# AS5040_SSI.net
KiCad netlist of a schematic drawn in EAGLE
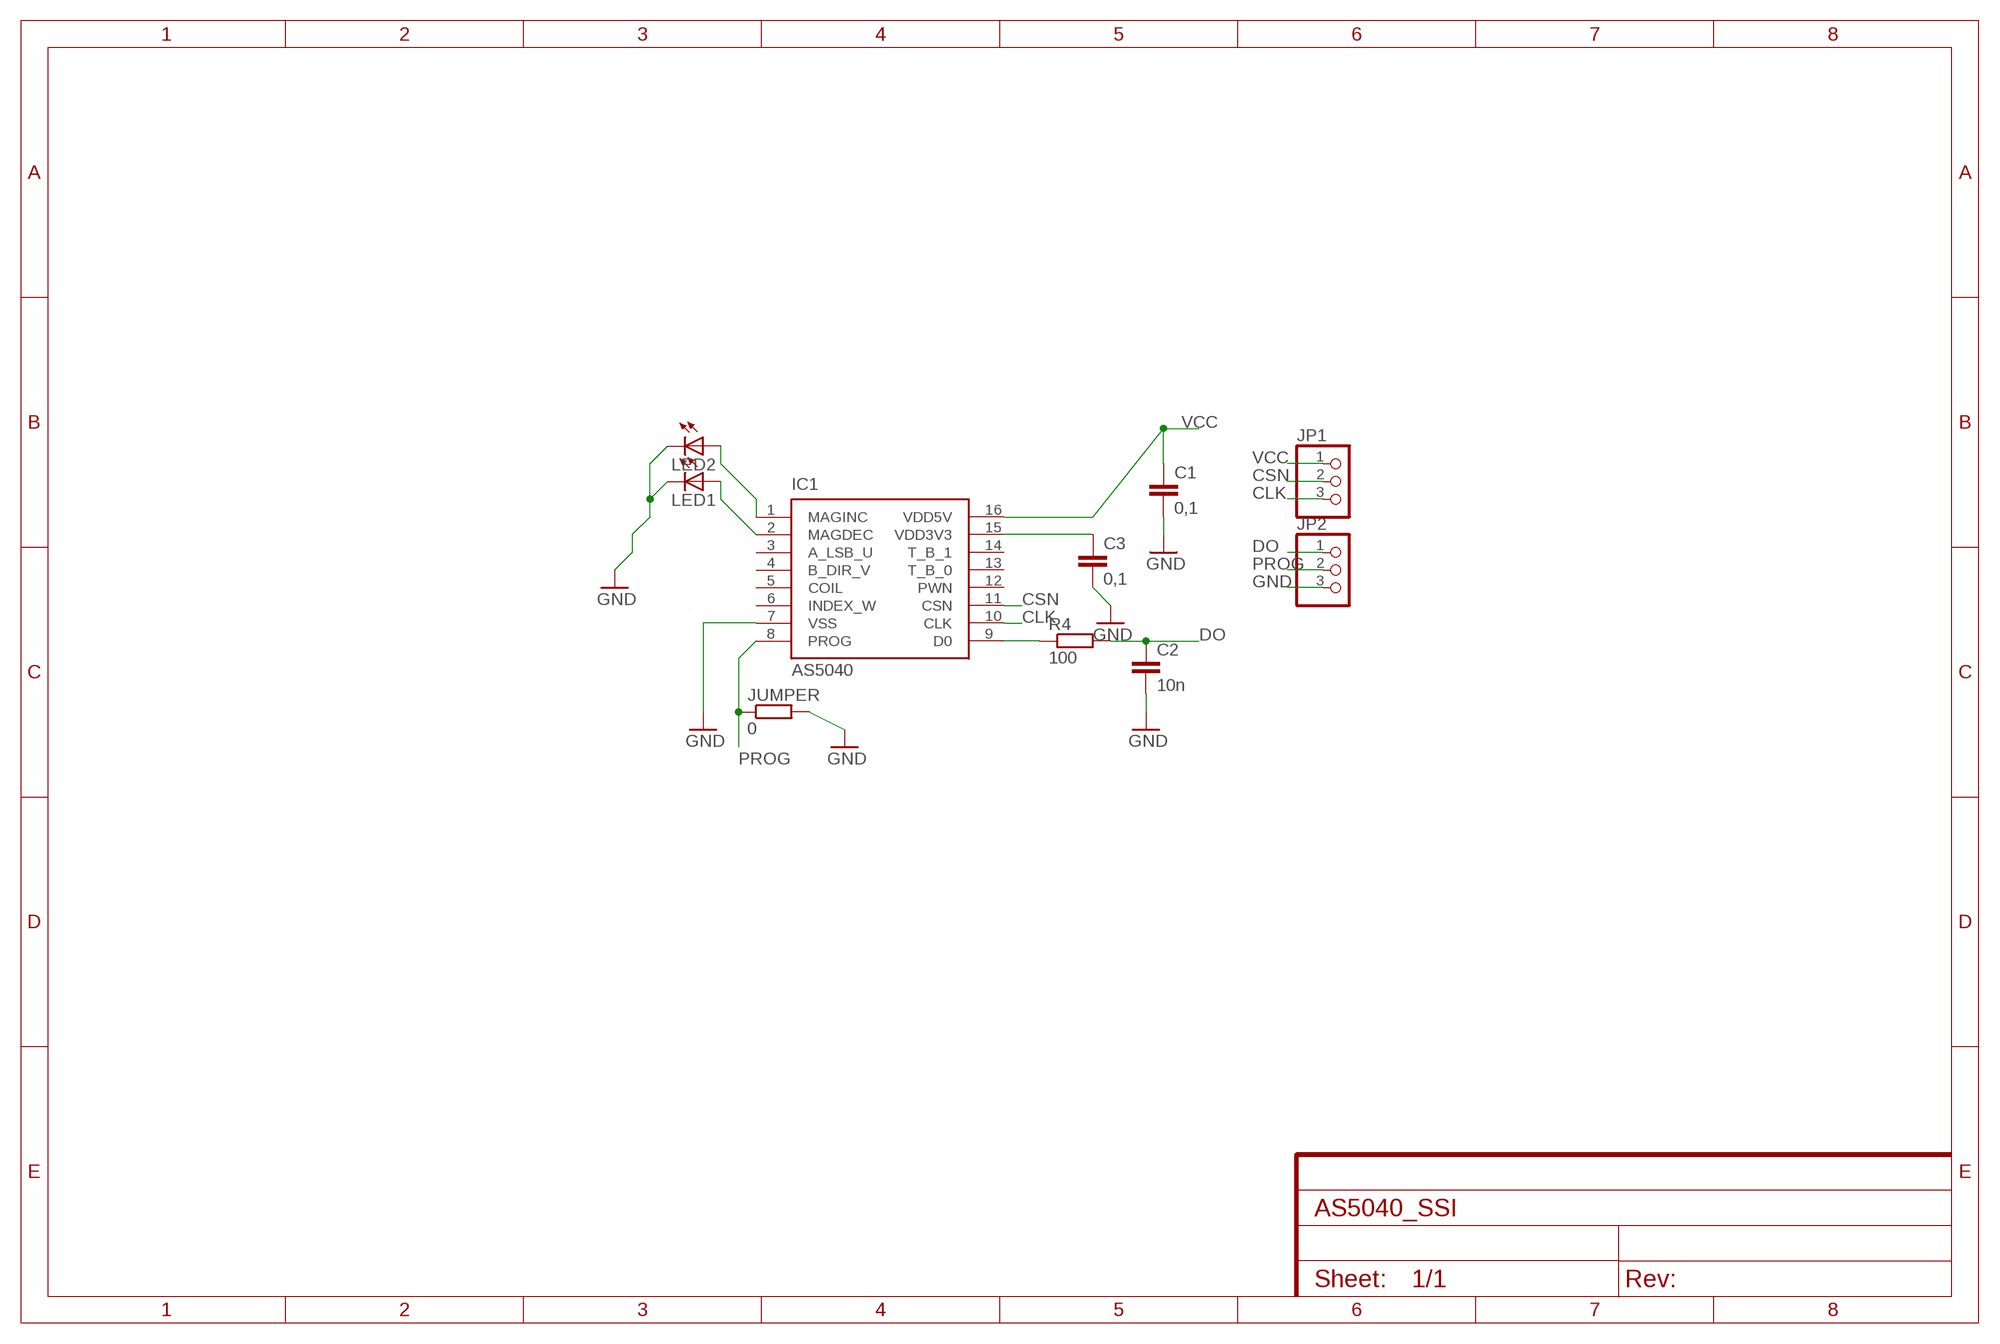
[diagram p0: schematic, sheet 1]

(export (version "E")
  (design (tool "Eeschema 10.0.6"))
  (components
    (comp (ref "C1")
      (value "0,1")
      (footprint "eagle-import:C0805")
      (libsource (lib "eagle-import") (part "C-EUC0805"))
    )
    (comp (ref "C2")
      (value "10n")
      (footprint "eagle-import:C0805")
      (libsource (lib "eagle-import") (part "C-EUC0805"))
    )
    (comp (ref "C3")
      (value "0,1")
      (footprint "eagle-import:C0805")
      (libsource (lib "eagle-import") (part "C-EUC0805"))
    )
    (comp (ref "IC1")
      (value "AS5040")
      (footprint "eagle-import:SSOP16")
      (fields (field (name "MPN") "AS5040ASSU"))
      (libsource (lib "eagle-import") (part "AS5040"))
    )
    (comp (ref "JP1")
      (value "PINHD-1X3")
      (footprint "eagle-import:1X03")
      (libsource (lib "eagle-import") (part "PINHD-1X3"))
    )
    (comp (ref "JP2")
      (value "PINHD-1X3")
      (footprint "eagle-import:1X03")
      (libsource (lib "eagle-import") (part "PINHD-1X3"))
    )
    (comp (ref "JUMPER")
      (value "0")
      (footprint "eagle-import:M0805")
      (libsource (lib "eagle-import") (part "R-EU_M0805"))
    )
    (comp (ref "LED1")
      (value "LEDCHIPLED_0805")
      (footprint "eagle-import:CHIPLED_0805")
      (libsource (lib "eagle-import") (part "LEDCHIPLED_0805"))
    )
    (comp (ref "LED2")
      (value "LEDCHIPLED_0805")
      (footprint "eagle-import:CHIPLED_0805")
      (libsource (lib "eagle-import") (part "LEDCHIPLED_0805"))
    )
    (comp (ref "R4")
      (value "100")
      (footprint "eagle-import:M0805")
      (libsource (lib "eagle-import") (part "R-EU_M0805"))
    )
  )
  (nets
    (net (code "1") (name "/CLK") (class "Default")
      (node (ref "IC1") (pin "10") (pinfunction "CLK_10") (pintype "input"))
      (node (ref "JP1") (pin "3") (pinfunction "3_3") (pintype "passive"))
    )
    (net (code "2") (name "/CSN") (class "Default")
      (node (ref "IC1") (pin "11") (pinfunction "CSN_11") (pintype "input"))
      (node (ref "JP1") (pin "2") (pinfunction "2_2") (pintype "passive"))
    )
    (net (code "3") (name "/DO") (class "Default")
      (node (ref "C2") (pin "1") (pinfunction "1_1") (pintype "passive"))
      (node (ref "JP2") (pin "1") (pinfunction "1_1") (pintype "passive"))
      (node (ref "R4") (pin "2") (pinfunction "2_2") (pintype "passive"))
    )
    (net (code "4") (name "/PROG") (class "Default")
      (node (ref "IC1") (pin "8") (pinfunction "PROG_8") (pintype "input"))
      (node (ref "JP2") (pin "2") (pinfunction "2_2") (pintype "passive"))
      (node (ref "JUMPER") (pin "1") (pinfunction "1_1") (pintype "passive"))
    )
    (net (code "5") (name "/VCC") (class "Default")
      (node (ref "C1") (pin "1") (pinfunction "1_1") (pintype "passive"))
      (node (ref "IC1") (pin "16") (pinfunction "VDD5V_16") (pintype "passive"))
      (node (ref "JP1") (pin "1") (pinfunction "1_1") (pintype "passive"))
    )
    (net (code "6") (name "GND") (class "Default")
      (node (ref "C1") (pin "2") (pinfunction "2_2") (pintype "passive"))
      (node (ref "C2") (pin "2") (pinfunction "2_2") (pintype "passive"))
      (node (ref "C3") (pin "2") (pinfunction "2_2") (pintype "passive"))
      (node (ref "IC1") (pin "7") (pinfunction "VSS_7") (pintype "passive"))
      (node (ref "JP2") (pin "3") (pinfunction "3_3") (pintype "passive"))
      (node (ref "JUMPER") (pin "2") (pinfunction "2_2") (pintype "passive"))
      (node (ref "LED1") (pin "C") (pinfunction "C_C") (pintype "passive"))
      (node (ref "LED2") (pin "C") (pinfunction "C_C") (pintype "passive"))
    )
    (net (code "7") (name "Net-(IC1-D0)") (class "Default")
      (node (ref "IC1") (pin "9") (pinfunction "D0_9") (pintype "tri_state"))
      (node (ref "R4") (pin "1") (pinfunction "1_1") (pintype "passive"))
    )
    (net (code "8") (name "Net-(IC1-MAGDEC)") (class "Default")
      (node (ref "IC1") (pin "2") (pinfunction "MAGDEC_2") (pintype "tri_state"))
      (node (ref "LED1") (pin "A") (pinfunction "A_A") (pintype "passive"))
    )
    (net (code "9") (name "Net-(IC1-MAGINC)") (class "Default")
      (node (ref "IC1") (pin "1") (pinfunction "MAGINC_1") (pintype "tri_state"))
      (node (ref "LED2") (pin "A") (pinfunction "A_A") (pintype "passive"))
    )
    (net (code "10") (name "Net-(IC1-VDD3V3)") (class "Default")
      (node (ref "C3") (pin "1") (pinfunction "1_1") (pintype "passive"))
      (node (ref "IC1") (pin "15") (pinfunction "VDD3V3_15") (pintype "passive"))
    )
    (net (code "11") (name "unconnected-(IC1-A_LSB_U-Pad3)") (class "Default")
      (node (ref "IC1") (pin "3") (pinfunction "A_LSB_U_3") (pintype "output"))
    )
    (net (code "12") (name "unconnected-(IC1-B_DIR_V-Pad4)") (class "Default")
      (node (ref "IC1") (pin "4") (pinfunction "B_DIR_V_4") (pintype "output"))
    )
    (net (code "13") (name "unconnected-(IC1-COIL-Pad5)") (class "Default")
      (node (ref "IC1") (pin "5") (pinfunction "COIL_5") (pintype "no_connect"))
    )
    (net (code "14") (name "unconnected-(IC1-INDEX_W-Pad6)") (class "Default")
      (node (ref "IC1") (pin "6") (pinfunction "INDEX_W_6") (pintype "output"))
    )
    (net (code "15") (name "unconnected-(IC1-PWN-Pad12)") (class "Default")
      (node (ref "IC1") (pin "12") (pinfunction "PWN_12") (pintype "passive"))
    )
    (net (code "16") (name "unconnected-(IC1-T_B_0-Pad13)") (class "Default")
      (node (ref "IC1") (pin "13") (pinfunction "T_B_0_13") (pintype "no_connect"))
    )
    (net (code "17") (name "unconnected-(IC1-T_B_1-Pad14)") (class "Default")
      (node (ref "IC1") (pin "14") (pinfunction "T_B_1_14") (pintype "no_connect"))
    )
  )
)
